# PWM_Controller_Half_Bridge_IR2110.net
KiCad netlist of a schematic drawn in Altium Designer
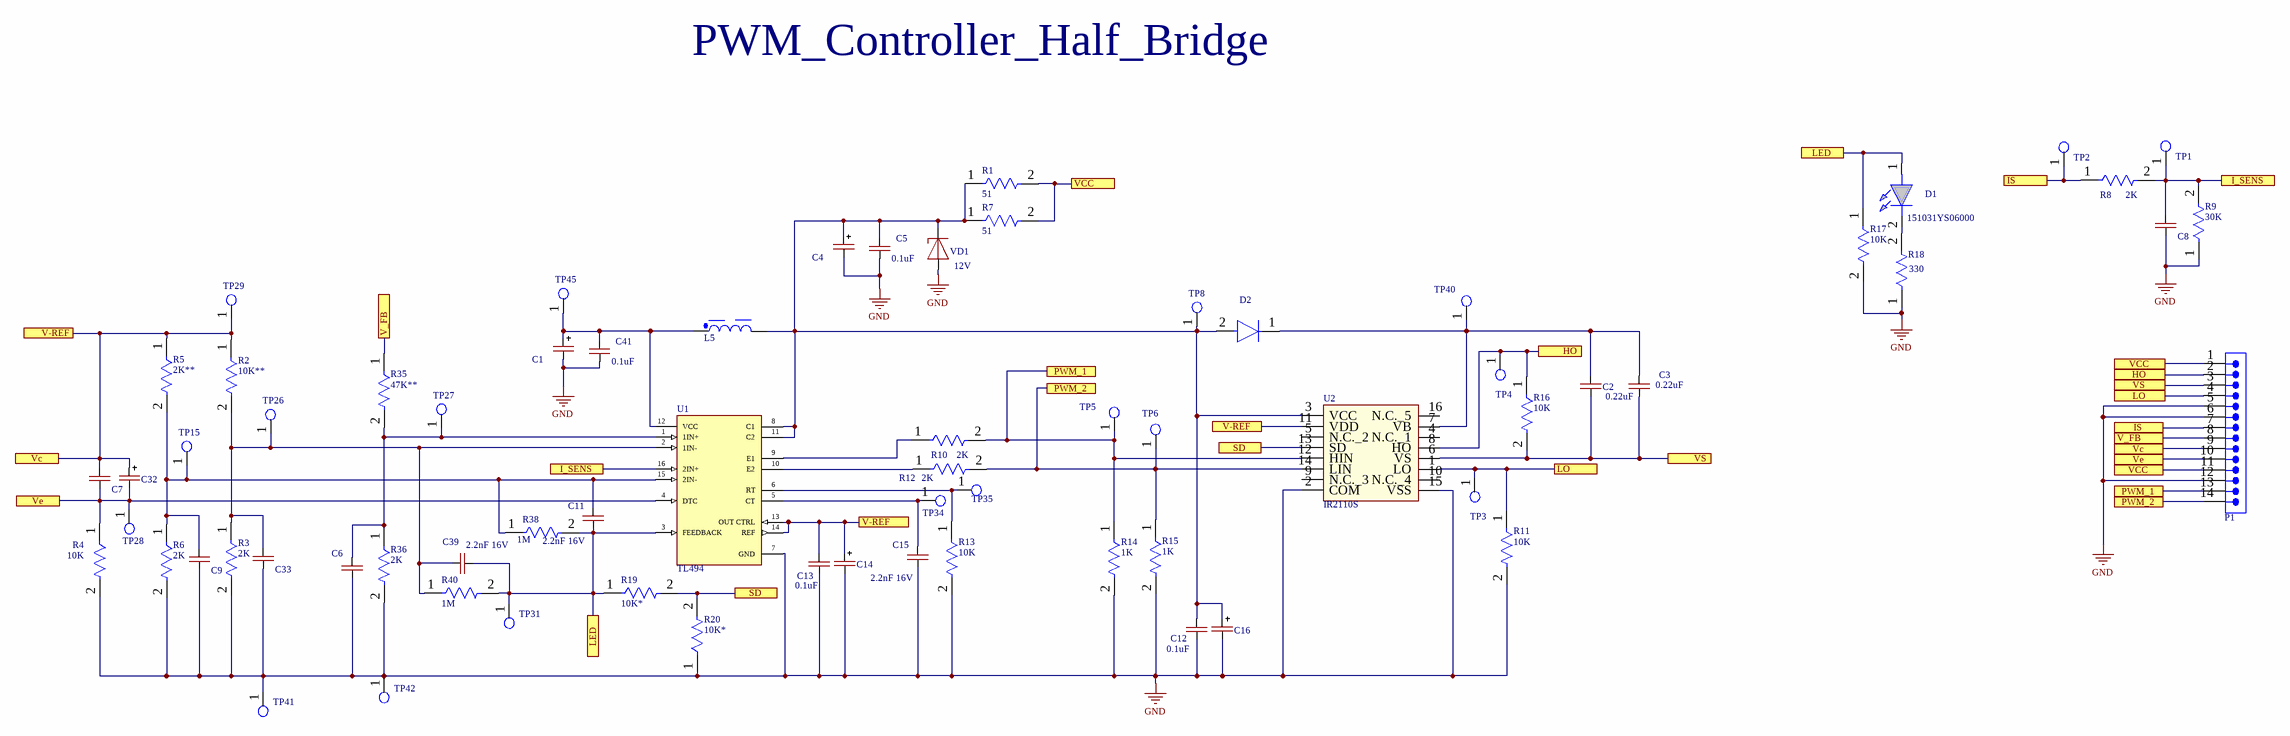
[diagram p0: PWM_Controller_Half_Bridge_IR2110.SchDoc]

(export (version "E")
  (design (tool "Eeschema 10.0.6"))
  (components
    (comp (ref "C1")
      (value "CAP-POLAR")
      (footprint "SIZE_EEE")
      (libsource (lib "PASSIVE_COMPONENTS") (part "CAP-POLAR"))
    )
    (comp (ref "C2")
      (value "0.22uF")
      (footprint "FP-C1210X475K5RACTU-IPC_C")
      (libsource (lib "PASSIVE_COMPONENTS") (part "CAP_1210"))
    )
    (comp (ref "C3")
      (value "0.22uF")
      (footprint "FP-C1210X475K5RACTU-IPC_C")
      (libsource (lib "PASSIVE_COMPONENTS") (part "CAP_1210"))
    )
    (comp (ref "C4")
      (value "CAP-POLAR")
      (footprint "SIZE_EEE")
      (libsource (lib "PASSIVE_COMPONENTS") (part "CAP-POLAR"))
    )
    (comp (ref "C5")
      (value "0.1uF")
      (footprint "CAP-0805")
      (libsource (lib "PASSIVE_COMPONENTS") (part "CAP-NON-POLAR"))
    )
    (comp (ref "C6")
      (value "CAP-NON-POLAR")
      (footprint "CAP-0805")
      (libsource (lib "PASSIVE_COMPONENTS") (part "CAP-NON-POLAR"))
    )
    (comp (ref "C7")
      (value "CAP-NON-POLAR")
      (footprint "CAP-0805")
      (libsource (lib "PASSIVE_COMPONENTS") (part "CAP-NON-POLAR"))
    )
    (comp (ref "C8")
      (value "CAP-NON-POLAR")
      (footprint "CAP-0805")
      (libsource (lib "PASSIVE_COMPONENTS") (part "CAP-NON-POLAR"))
    )
    (comp (ref "C9")
      (value "CAP-NON-POLAR")
      (footprint "CAP-0805")
      (libsource (lib "PASSIVE_COMPONENTS") (part "CAP-NON-POLAR"))
    )
    (comp (ref "C11")
      (value "2.2nF 16V")
      (footprint "CAP-0805")
      (libsource (lib "PASSIVE_COMPONENTS") (part "CAP-NON-POLAR"))
    )
    (comp (ref "C12")
      (value "0.1uF")
      (footprint "CAP-0805")
      (libsource (lib "PASSIVE_COMPONENTS") (part "CAP-NON-POLAR"))
    )
    (comp (ref "C13")
      (value "0.1uF")
      (footprint "CAP-0805")
      (libsource (lib "PASSIVE_COMPONENTS") (part "CAP-NON-POLAR"))
    )
    (comp (ref "C14")
      (value "CAP-POLAR")
      (footprint "CAP-TAN-D")
      (libsource (lib "PASSIVE_COMPONENTS") (part "CAP-POLAR"))
    )
    (comp (ref "C15")
      (value "2.2nF 16V")
      (footprint "CAP-0805")
      (libsource (lib "PASSIVE_COMPONENTS") (part "CAP-NON-POLAR"))
    )
    (comp (ref "C16")
      (value "CAP-POLAR")
      (footprint "CAP-TAN-D")
      (libsource (lib "PASSIVE_COMPONENTS") (part "CAP-POLAR"))
    )
    (comp (ref "C32")
      (value "CAP-POLAR")
      (footprint "CAP-TAN-D")
      (libsource (lib "PASSIVE_COMPONENTS") (part "CAP-POLAR"))
    )
    (comp (ref "C33")
      (value "CAP-NON-POLAR")
      (footprint "CAP-0805")
      (libsource (lib "PASSIVE_COMPONENTS") (part "CAP-NON-POLAR"))
    )
    (comp (ref "C39")
      (value "2.2nF 16V")
      (footprint "CAP-0805")
      (libsource (lib "PASSIVE_COMPONENTS") (part "CAP-NON-POLAR"))
    )
    (comp (ref "C41")
      (value "0.1uF")
      (footprint "CAP-0805")
      (libsource (lib "PASSIVE_COMPONENTS") (part "CAP-NON-POLAR"))
    )
    (comp (ref "D1")
      (value "151031YS06000")
      (footprint "LED_RED")
      (description "WURTH ELEKTRONIK - 151031YS06000 - LED, Yellow, Through Hole, T-1 (3mm), 30 mA, 2 V, 590 nm")
      (fields (field (name "MOUSER PART NUMBER") "710-151031YS06000"))
      (libsource (lib "Optic-LED") (part "LED"))
    )
    (comp (ref "D2") (value "US1G") (footprint "DO-214AA") (libsource (lib "Diodes") (part "US1G")))
    (comp (ref "L5")
      (value "47µH, 1.17A")
      (footprint "WE-PD2_7850")
      (description "WE-PD2 SMT Power Inductor, size 7850, 47µH, 1.17A, 0.18Ω")
      (fields
        (field (name "MANUFACTURER PART NUMBER") "744775147")
        (field (name "MANUFACTURER") "Wurth Elektronik")
      )
      (libsource (lib "WE-PD2 (rev22d)") (part "744775147"))
    )
    (comp (ref "P1")
      (value "61301411021")
      (footprint "61301411021")
      (description "WR-PHD Pin Header, THT, Angled, pitch 2.54mm, 1 Row, 14P")
      (fields (field (name "MANUFACTURER") "Wurth Elektronik"))
      (libsource (lib "Altium_WR-PHD (rev22b)") (part "61301411021"))
    )
    (comp (ref "R1")
      (value "51")
      (footprint "FP-RMCF1210-MFG")
      (description "51Ω ±5% 0.5W 1210 Thick Film Chip Resistor AEC-Q200 compliant")
      (fields (field (name "TOLERANCE") "5%"))
      (libsource (lib "Altium Content Vault") (part "1029c3af85768c4190bb7ad29bc67b5"))
    )
    (comp (ref "R2")
      (value "10K**")
      (footprint "RES-0805")
      (description "10K")
      (libsource (lib "PASSIVE_COMPONENTS") (part "RES-CONST"))
    )
    (comp (ref "R3")
      (value "2K")
      (footprint "RES-0805")
      (libsource (lib "PASSIVE_COMPONENTS") (part "RES-CONST"))
    )
    (comp (ref "R4")
      (value "10K")
      (footprint "RES-0805")
      (libsource (lib "PASSIVE_COMPONENTS") (part "RES-CONST"))
    )
    (comp (ref "R5")
      (value "2K**")
      (footprint "RES-0805")
      (description "2K")
      (libsource (lib "PASSIVE_COMPONENTS") (part "RES-CONST"))
    )
    (comp (ref "R6")
      (value "2K")
      (footprint "RES-0805")
      (libsource (lib "PASSIVE_COMPONENTS") (part "RES-CONST"))
    )
    (comp (ref "R7")
      (value "51")
      (footprint "FP-RMCF1210-MFG")
      (description "51Ω ±5% 0.5W 1210 Thick Film Chip Resistor AEC-Q200 compliant")
      (fields (field (name "TOLERANCE") "5%"))
      (libsource (lib "Altium Content Vault") (part "1029c3af85768c4190bb7ad29bc67b5"))
    )
    (comp (ref "R8")
      (value "2K")
      (footprint "RES-0805")
      (libsource (lib "PASSIVE_COMPONENTS") (part "RES-CONST"))
    )
    (comp (ref "R9")
      (value "30K")
      (footprint "RES-0805")
      (libsource (lib "PASSIVE_COMPONENTS") (part "RES-CONST"))
    )
    (comp (ref "R10")
      (value "2K")
      (footprint "RES-0805")
      (libsource (lib "PASSIVE_COMPONENTS") (part "RES-CONST"))
    )
    (comp (ref "R11")
      (value "10K")
      (footprint "RES-0805")
      (libsource (lib "PASSIVE_COMPONENTS") (part "RES-CONST"))
    )
    (comp (ref "R12")
      (value "2K")
      (footprint "RES-0805")
      (libsource (lib "PASSIVE_COMPONENTS") (part "RES-CONST"))
    )
    (comp (ref "R13")
      (value "10K")
      (footprint "RES-0805")
      (libsource (lib "PASSIVE_COMPONENTS") (part "RES-CONST"))
    )
    (comp (ref "R14")
      (value "1K")
      (footprint "RES-0805")
      (libsource (lib "PASSIVE_COMPONENTS") (part "RES-CONST"))
    )
    (comp (ref "R15")
      (value "1K")
      (footprint "RES-0805")
      (libsource (lib "PASSIVE_COMPONENTS") (part "RES-CONST"))
    )
    (comp (ref "R16")
      (value "10K")
      (footprint "RES-0805")
      (libsource (lib "PASSIVE_COMPONENTS") (part "RES-CONST"))
    )
    (comp (ref "R17")
      (value "10K")
      (footprint "RES-0805")
      (libsource (lib "PASSIVE_COMPONENTS") (part "RES-CONST"))
    )
    (comp (ref "R18")
      (value "330")
      (footprint "RES-0805")
      (libsource (lib "PASSIVE_COMPONENTS") (part "RES-CONST"))
    )
    (comp (ref "R19")
      (value "10K*")
      (footprint "RES-0805")
      (description "10K")
      (libsource (lib "PASSIVE_COMPONENTS") (part "RES-CONST"))
    )
    (comp (ref "R20")
      (value "10K*")
      (footprint "RES-0805")
      (description "10K")
      (libsource (lib "PASSIVE_COMPONENTS") (part "RES-CONST"))
    )
    (comp (ref "R35")
      (value "47K**")
      (footprint "RES-0805")
      (description "47K")
      (libsource (lib "PASSIVE_COMPONENTS") (part "RES-CONST"))
    )
    (comp (ref "R36")
      (value "2K")
      (footprint "RES-0805")
      (libsource (lib "PASSIVE_COMPONENTS") (part "RES-CONST"))
    )
    (comp (ref "R38")
      (value "1M")
      (footprint "RES-0805")
      (libsource (lib "PASSIVE_COMPONENTS") (part "RES-CONST"))
    )
    (comp (ref "R40")
      (value "1M")
      (footprint "RES-0805")
      (libsource (lib "PASSIVE_COMPONENTS") (part "RES-CONST"))
    )
    (comp (ref "TP1")
      (value "~")
      (footprint "Test_Point")
      (description "Test_Point")
      (libsource (lib "Connectors") (part "TP_PCB?"))
    )
    (comp (ref "TP2")
      (value "~")
      (footprint "Test_Point")
      (description "Test_Point")
      (libsource (lib "Connectors") (part "TP_PCB?"))
    )
    (comp (ref "TP3")
      (value "~")
      (footprint "Test_Point")
      (description "Test_Point")
      (libsource (lib "Connectors") (part "TP_PCB?"))
    )
    (comp (ref "TP4")
      (value "~")
      (footprint "Test_Point")
      (description "Test_Point")
      (libsource (lib "Connectors") (part "TP_PCB?"))
    )
    (comp (ref "TP5")
      (value "~")
      (footprint "Test_Point")
      (description "Test_Point")
      (libsource (lib "Connectors") (part "TP_PCB?"))
    )
    (comp (ref "TP6")
      (value "~")
      (footprint "Test_Point")
      (description "Test_Point")
      (libsource (lib "Connectors") (part "TP_PCB?"))
    )
    (comp (ref "TP8")
      (value "~")
      (footprint "Test_Point")
      (description "Test_Point")
      (libsource (lib "Connectors") (part "TP_PCB?"))
    )
    (comp (ref "TP15")
      (value "~")
      (footprint "Test_Point")
      (description "Test_Point")
      (libsource (lib "Connectors") (part "TP_PCB?"))
    )
    (comp (ref "TP26")
      (value "~")
      (footprint "Test_Point")
      (description "Test_Point")
      (libsource (lib "Connectors") (part "TP_PCB?"))
    )
    (comp (ref "TP27")
      (value "~")
      (footprint "Test_Point")
      (description "Test_Point")
      (libsource (lib "Connectors") (part "TP_PCB?"))
    )
    (comp (ref "TP28")
      (value "~")
      (footprint "Test_Point")
      (description "Test_Point")
      (libsource (lib "Connectors") (part "TP_PCB?"))
    )
    (comp (ref "TP29")
      (value "~")
      (footprint "Test_Point")
      (description "Test_Point")
      (libsource (lib "Connectors") (part "TP_PCB?"))
    )
    (comp (ref "TP31")
      (value "~")
      (footprint "Test_Point")
      (description "Test_Point")
      (libsource (lib "Connectors") (part "TP_PCB?"))
    )
    (comp (ref "TP34")
      (value "~")
      (footprint "Test_Point")
      (description "Test_Point")
      (libsource (lib "Connectors") (part "TP_PCB?"))
    )
    (comp (ref "TP35")
      (value "~")
      (footprint "Test_Point")
      (description "Test_Point")
      (libsource (lib "Connectors") (part "TP_PCB?"))
    )
    (comp (ref "TP40")
      (value "~")
      (footprint "Test_Point")
      (description "Test_Point")
      (libsource (lib "Connectors") (part "TP_PCB?"))
    )
    (comp (ref "TP41")
      (value "~")
      (footprint "Test_Point")
      (description "Test_Point")
      (libsource (lib "Connectors") (part "TP_PCB?"))
    )
    (comp (ref "TP42")
      (value "~")
      (footprint "Test_Point")
      (description "Test_Point")
      (libsource (lib "Connectors") (part "TP_PCB?"))
    )
    (comp (ref "TP45")
      (value "~")
      (footprint "Test_Point")
      (description "Test_Point")
      (libsource (lib "Connectors") (part "TP_PCB?"))
    )
    (comp (ref "U1")
      (value "TL494")
      (footprint "SOIC-16-M")
      (description "TL494 Pwm controller")
      (libsource (lib "Integrated_Circuts") (part "TL494"))
    )
    (comp (ref "U2")
      (value "IR2110S")
      (footprint "SOIC127P1036X391-16N")
      (description "IC DRIVER HIGH/LOW SIDE 16-SOIC")
      (libsource (lib "Integrated_Circuts") (part "IR2110S"))
    )
    (comp (ref "VD1") (value "12V") (footprint "DO-017AA") (libsource (lib "Diodes") (part "ZENER")))
  )
  (nets
    (net (code "1") (name "/HO") (class "Default")
      (node (ref "P1") (pin "2") (pinfunction "2_2") (pintype "passive"))
      (node (ref "R16") (pin "1") (pinfunction "1_1") (pintype "passive"))
      (node (ref "TP4") (pin "1") (pinfunction "G9_1") (pintype "passive"))
      (node (ref "U2") (pin "8") (pinfunction "HO_8") (pintype "passive"))
    )
    (net (code "2") (name "/IS") (class "Default")
      (node (ref "P1") (pin "7") (pinfunction "7_7") (pintype "passive"))
      (node (ref "R8") (pin "1") (pinfunction "1_1") (pintype "passive"))
      (node (ref "TP2") (pin "1") (pinfunction "G9_1") (pintype "passive"))
    )
    (net (code "3") (name "/I_SENS") (class "Default")
      (node (ref "C8") (pin "2") (pinfunction "2_2") (pintype "passive"))
      (node (ref "R8") (pin "2") (pinfunction "2_2") (pintype "passive"))
      (node (ref "R9") (pin "2") (pinfunction "2_2") (pintype "passive"))
      (node (ref "TP1") (pin "1") (pinfunction "G9_1") (pintype "passive"))
      (node (ref "U1") (pin "16") (pinfunction "2IN+_16") (pintype "input"))
    )
    (net (code "4") (name "/LED") (class "Default")
      (node (ref "C11") (pin "1") (pinfunction "1_1") (pintype "passive"))
      (node (ref "C39") (pin "1") (pinfunction "1_1") (pintype "passive"))
      (node (ref "D1") (pin "1") (pinfunction "A_1") (pintype "passive"))
      (node (ref "R17") (pin "1") (pinfunction "1_1") (pintype "passive"))
      (node (ref "R19") (pin "1") (pinfunction "1_1") (pintype "passive"))
      (node (ref "R38") (pin "2") (pinfunction "2_2") (pintype "passive"))
      (node (ref "R40") (pin "2") (pinfunction "2_2") (pintype "passive"))
      (node (ref "TP31") (pin "1") (pinfunction "G9_1") (pintype "passive"))
      (node (ref "U1") (pin "3") (pinfunction "FEEDBACK_3") (pintype "input"))
    )
    (net (code "5") (name "/LO") (class "Default")
      (node (ref "P1") (pin "4") (pinfunction "4_4") (pintype "passive"))
      (node (ref "R11") (pin "1") (pinfunction "1_1") (pintype "passive"))
      (node (ref "TP3") (pin "1") (pinfunction "G9_1") (pintype "passive"))
      (node (ref "U2") (pin "1") (pinfunction "LO_1") (pintype "passive"))
    )
    (net (code "6") (name "/PWM_1") (class "Default")
      (node (ref "P1") (pin "13") (pinfunction "13_13") (pintype "passive"))
      (node (ref "R10") (pin "2") (pinfunction "2_2") (pintype "passive"))
      (node (ref "R14") (pin "1") (pinfunction "1_1") (pintype "passive"))
      (node (ref "TP5") (pin "1") (pinfunction "G9_1") (pintype "passive"))
      (node (ref "U2") (pin "12") (pinfunction "HIN_12") (pintype "passive"))
    )
    (net (code "7") (name "/PWM_2") (class "Default")
      (node (ref "P1") (pin "14") (pinfunction "14_14") (pintype "passive"))
      (node (ref "R12") (pin "2") (pinfunction "2_2") (pintype "passive"))
      (node (ref "R15") (pin "1") (pinfunction "1_1") (pintype "passive"))
      (node (ref "TP6") (pin "1") (pinfunction "G9_1") (pintype "passive"))
      (node (ref "U2") (pin "14") (pinfunction "LIN_14") (pintype "passive"))
    )
    (net (code "8") (name "/SD") (class "Default")
      (node (ref "R19") (pin "2") (pinfunction "2_2") (pintype "passive"))
      (node (ref "R20") (pin "2") (pinfunction "2_2") (pintype "passive"))
      (node (ref "U2") (pin "13") (pinfunction "SD_13") (pintype "passive"))
    )
    (net (code "9") (name "/V-REF") (class "Default")
      (node (ref "C13") (pin "2") (pinfunction "2_2") (pintype "passive"))
      (node (ref "C14") (pin "1") (pinfunction "+_1") (pintype "passive"))
      (node (ref "C32") (pin "1") (pinfunction "+_1") (pintype "passive"))
      (node (ref "C7") (pin "2") (pinfunction "2_2") (pintype "passive"))
      (node (ref "P1") (pin "9") (pinfunction "9_9") (pintype "passive"))
      (node (ref "R2") (pin "1") (pinfunction "1_1") (pintype "passive"))
      (node (ref "R5") (pin "1") (pinfunction "1_1") (pintype "passive"))
      (node (ref "TP29") (pin "1") (pinfunction "G9_1") (pintype "passive"))
      (node (ref "U1") (pin "13") (pinfunction "OUT_CTRL_13") (pintype "input"))
      (node (ref "U1") (pin "14") (pinfunction "REF_14") (pintype "output"))
      (node (ref "U2") (pin "11") (pinfunction "VDD_11") (pintype "passive"))
    )
    (net (code "10") (name "/VCC") (class "Default")
      (node (ref "P1") (pin "1") (pinfunction "1_1") (pintype "passive"))
      (node (ref "P1") (pin "11") (pinfunction "11_11") (pintype "passive"))
      (node (ref "R1") (pin "2") (pinfunction "2_2") (pintype "passive"))
      (node (ref "R7") (pin "2") (pinfunction "2_2") (pintype "passive"))
    )
    (net (code "11") (name "/VS") (class "Default")
      (node (ref "C2") (pin "1") (pinfunction "1_1") (pintype "passive"))
      (node (ref "C3") (pin "1") (pinfunction "1_1") (pintype "passive"))
      (node (ref "P1") (pin "3") (pinfunction "3_3") (pintype "passive"))
      (node (ref "R16") (pin "2") (pinfunction "2_2") (pintype "passive"))
      (node (ref "U2") (pin "6") (pinfunction "VS_6") (pintype "passive"))
    )
    (net (code "12") (name "/V_FB") (class "Default")
      (node (ref "P1") (pin "8") (pinfunction "8_8") (pintype "passive"))
      (node (ref "R35") (pin "1") (pinfunction "1_1") (pintype "passive"))
    )
    (net (code "13") (name "/Ve") (class "Default")
      (node (ref "C32") (pin "2") (pinfunction "-_2") (pintype "passive"))
      (node (ref "C7") (pin "1") (pinfunction "1_1") (pintype "passive"))
      (node (ref "P1") (pin "10") (pinfunction "10_10") (pintype "passive"))
      (node (ref "R4") (pin "1") (pinfunction "1_1") (pintype "passive"))
      (node (ref "TP28") (pin "1") (pinfunction "G9_1") (pintype "passive"))
      (node (ref "U1") (pin "4") (pinfunction "DTC_4") (pintype "input"))
    )
    (net (code "14") (name "GND") (class "Default")
      (node (ref "C1") (pin "2") (pinfunction "-_2") (pintype "passive"))
      (node (ref "C12") (pin "1") (pinfunction "1_1") (pintype "passive"))
      (node (ref "C13") (pin "1") (pinfunction "1_1") (pintype "passive"))
      (node (ref "C14") (pin "2") (pinfunction "-_2") (pintype "passive"))
      (node (ref "C15") (pin "1") (pinfunction "1_1") (pintype "passive"))
      (node (ref "C16") (pin "2") (pinfunction "-_2") (pintype "passive"))
      (node (ref "C33") (pin "1") (pinfunction "1_1") (pintype "passive"))
      (node (ref "C4") (pin "2") (pinfunction "-_2") (pintype "passive"))
      (node (ref "C41") (pin "1") (pinfunction "1_1") (pintype "passive"))
      (node (ref "C5") (pin "1") (pinfunction "1_1") (pintype "passive"))
      (node (ref "C6") (pin "1") (pinfunction "1_1") (pintype "passive"))
      (node (ref "C8") (pin "1") (pinfunction "1_1") (pintype "passive"))
      (node (ref "C9") (pin "1") (pinfunction "1_1") (pintype "passive"))
      (node (ref "P1") (pin "12") (pinfunction "12_12") (pintype "passive"))
      (node (ref "P1") (pin "5") (pinfunction "5_5") (pintype "passive"))
      (node (ref "P1") (pin "6") (pinfunction "6_6") (pintype "passive"))
      (node (ref "R11") (pin "2") (pinfunction "2_2") (pintype "passive"))
      (node (ref "R13") (pin "2") (pinfunction "2_2") (pintype "passive"))
      (node (ref "R14") (pin "2") (pinfunction "2_2") (pintype "passive"))
      (node (ref "R15") (pin "2") (pinfunction "2_2") (pintype "passive"))
      (node (ref "R17") (pin "2") (pinfunction "2_2") (pintype "passive"))
      (node (ref "R18") (pin "1") (pinfunction "1_1") (pintype "passive"))
      (node (ref "R20") (pin "1") (pinfunction "1_1") (pintype "passive"))
      (node (ref "R3") (pin "2") (pinfunction "2_2") (pintype "passive"))
      (node (ref "R36") (pin "2") (pinfunction "2_2") (pintype "passive"))
      (node (ref "R4") (pin "2") (pinfunction "2_2") (pintype "passive"))
      (node (ref "R6") (pin "2") (pinfunction "2_2") (pintype "passive"))
      (node (ref "R9") (pin "1") (pinfunction "1_1") (pintype "passive"))
      (node (ref "TP41") (pin "1") (pinfunction "G9_1") (pintype "passive"))
      (node (ref "TP42") (pin "1") (pinfunction "G9_1") (pintype "passive"))
      (node (ref "U1") (pin "7") (pinfunction "GND_7") (pintype "power_in"))
      (node (ref "U2") (pin "15") (pinfunction "VSS_15") (pintype "passive"))
      (node (ref "U2") (pin "2") (pinfunction "COM_2") (pintype "passive"))
      (node (ref "VD1") (pin "2") (pinfunction "A_2") (pintype "passive"))
    )
    (net (code "15") (name "Net-(C1-+)") (class "Default")
      (node (ref "C1") (pin "1") (pinfunction "+_1") (pintype "passive"))
      (node (ref "C41") (pin "2") (pinfunction "2_2") (pintype "passive"))
      (node (ref "L5") (pin "1") (pinfunction "1_1") (pintype "passive"))
      (node (ref "TP45") (pin "1") (pinfunction "G9_1") (pintype "passive"))
      (node (ref "U1") (pin "12") (pinfunction "VCC_12") (pintype "power_in"))
    )
    (net (code "16") (name "Net-(C16-+)") (class "Default")
      (node (ref "C12") (pin "2") (pinfunction "2_2") (pintype "passive"))
      (node (ref "C16") (pin "1") (pinfunction "+_1") (pintype "passive"))
      (node (ref "C4") (pin "1") (pinfunction "+_1") (pintype "passive"))
      (node (ref "C5") (pin "2") (pinfunction "2_2") (pintype "passive"))
      (node (ref "D2") (pin "2") (pinfunction "A_2") (pintype "passive"))
      (node (ref "L5") (pin "2") (pinfunction "2_2") (pintype "passive"))
      (node (ref "R1") (pin "1") (pinfunction "1_1") (pintype "passive"))
      (node (ref "R7") (pin "1") (pinfunction "1_1") (pintype "passive"))
      (node (ref "TP8") (pin "1") (pinfunction "G9_1") (pintype "passive"))
      (node (ref "U1") (pin "11") (pinfunction "C2_11") (pintype "passive"))
      (node (ref "U1") (pin "8") (pinfunction "C1_8") (pintype "passive"))
      (node (ref "U2") (pin "3") (pinfunction "VCC_3") (pintype "passive"))
      (node (ref "VD1") (pin "1") (pinfunction "C_1") (pintype "passive"))
    )
    (net (code "17") (name "Net-(D1-K)") (class "Default")
      (node (ref "D1") (pin "2") (pinfunction "K_2") (pintype "passive"))
      (node (ref "R18") (pin "2") (pinfunction "2_2") (pintype "passive"))
    )
    (net (code "18") (name "Net-(D2-C)") (class "Default")
      (node (ref "C2") (pin "2") (pinfunction "2_2") (pintype "passive"))
      (node (ref "C3") (pin "2") (pinfunction "2_2") (pintype "passive"))
      (node (ref "D2") (pin "1") (pinfunction "C_1") (pintype "passive"))
      (node (ref "TP40") (pin "1") (pinfunction "G9_1") (pintype "passive"))
      (node (ref "U2") (pin "7") (pinfunction "VB_7") (pintype "passive"))
    )
    (net (code "19") (name "Net-(TP15-G9)") (class "Default")
      (node (ref "C11") (pin "2") (pinfunction "2_2") (pintype "passive"))
      (node (ref "C9") (pin "2") (pinfunction "2_2") (pintype "passive"))
      (node (ref "R38") (pin "1") (pinfunction "1_1") (pintype "passive"))
      (node (ref "R5") (pin "2") (pinfunction "2_2") (pintype "passive"))
      (node (ref "R6") (pin "1") (pinfunction "1_1") (pintype "passive"))
      (node (ref "TP15") (pin "1") (pinfunction "G9_1") (pintype "passive"))
      (node (ref "U1") (pin "15") (pinfunction "2IN-_15") (pintype "input"))
    )
    (net (code "20") (name "Net-(TP26-G9)") (class "Default")
      (node (ref "C33") (pin "2") (pinfunction "2_2") (pintype "passive"))
      (node (ref "C39") (pin "2") (pinfunction "2_2") (pintype "passive"))
      (node (ref "R2") (pin "2") (pinfunction "2_2") (pintype "passive"))
      (node (ref "R3") (pin "1") (pinfunction "1_1") (pintype "passive"))
      (node (ref "R40") (pin "1") (pinfunction "1_1") (pintype "passive"))
      (node (ref "TP26") (pin "1") (pinfunction "G9_1") (pintype "passive"))
      (node (ref "U1") (pin "2") (pinfunction "1IN-_2") (pintype "input"))
    )
    (net (code "21") (name "Net-(TP27-G9)") (class "Default")
      (node (ref "C6") (pin "2") (pinfunction "2_2") (pintype "passive"))
      (node (ref "R35") (pin "2") (pinfunction "2_2") (pintype "passive"))
      (node (ref "R36") (pin "1") (pinfunction "1_1") (pintype "passive"))
      (node (ref "TP27") (pin "1") (pinfunction "G9_1") (pintype "passive"))
      (node (ref "U1") (pin "1") (pinfunction "1IN+_1") (pintype "input"))
    )
    (net (code "22") (name "Net-(TP34-G9)") (class "Default")
      (node (ref "C15") (pin "2") (pinfunction "2_2") (pintype "passive"))
      (node (ref "TP34") (pin "1") (pinfunction "G9_1") (pintype "passive"))
      (node (ref "U1") (pin "5") (pinfunction "CT_5") (pintype "passive"))
    )
    (net (code "23") (name "Net-(TP35-G9)") (class "Default")
      (node (ref "R13") (pin "1") (pinfunction "1_1") (pintype "passive"))
      (node (ref "TP35") (pin "1") (pinfunction "G9_1") (pintype "passive"))
      (node (ref "U1") (pin "6") (pinfunction "RT_6") (pintype "passive"))
    )
    (net (code "24") (name "Net-(U1-E1)") (class "Default")
      (node (ref "R10") (pin "1") (pinfunction "1_1") (pintype "passive"))
      (node (ref "U1") (pin "9") (pinfunction "E1_9") (pintype "passive"))
    )
    (net (code "25") (name "Net-(U1-E2)") (class "Default")
      (node (ref "R12") (pin "1") (pinfunction "1_1") (pintype "passive"))
      (node (ref "U1") (pin "10") (pinfunction "E2_10") (pintype "passive"))
    )
    (net (code "26") (name "unconnected-(U2-N.C._1-Pad4)") (class "Default")
      (node (ref "U2") (pin "4") (pinfunction "N.C._1_4") (pintype "passive"))
    )
    (net (code "27") (name "unconnected-(U2-N.C._2-Pad5)") (class "Default")
      (node (ref "U2") (pin "5") (pinfunction "N.C._2_5") (pintype "passive"))
    )
    (net (code "28") (name "unconnected-(U2-N.C._3-Pad9)") (class "Default")
      (node (ref "U2") (pin "9") (pinfunction "N.C._3_9") (pintype "passive"))
    )
    (net (code "29") (name "unconnected-(U2-N.C._4-Pad10)") (class "Default")
      (node (ref "U2") (pin "10") (pinfunction "N.C._4_10") (pintype "passive"))
    )
    (net (code "30") (name "unconnected-(U2-N.C._5-Pad16)") (class "Default")
      (node (ref "U2") (pin "16") (pinfunction "N.C._5_16") (pintype "passive"))
    )
  )
)
